# Controlador_PID_digital.net
KiCad netlist of a schematic drawn in EAGLE
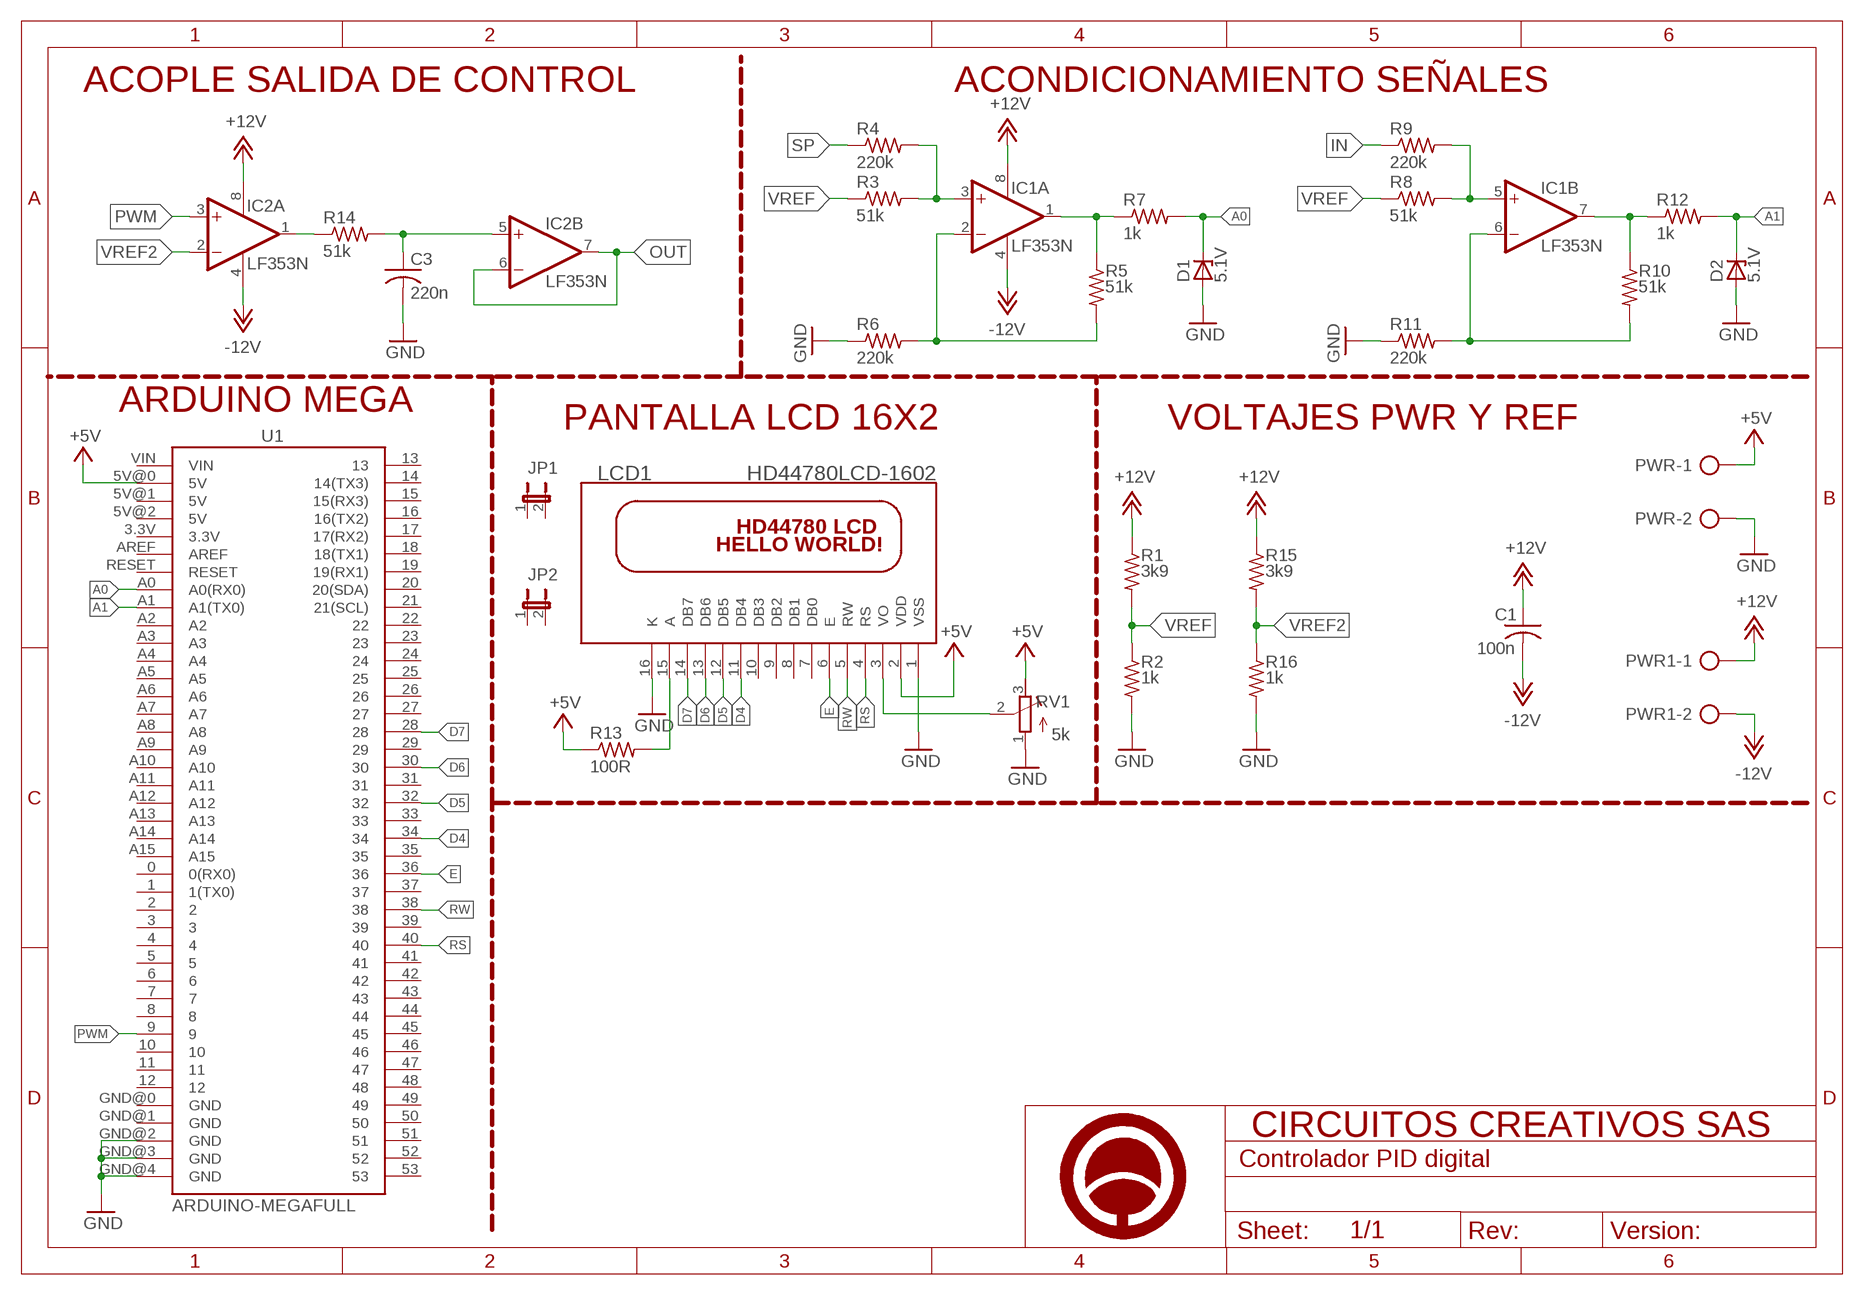
[diagram p0: schematic, sheet 1]

(export (version "E")
  (design (tool "Eeschema 10.0.6"))
  (components
    (comp (ref "C1")
      (value "100n")
      (footprint "eagle-import:C025-025X050")
      (libsource (lib "eagle-import") (part "C-US025-025X050"))
    )
    (comp (ref "C3")
      (value "220n")
      (footprint "eagle-import:C050-030X075")
      (libsource (lib "eagle-import") (part "C-US050-030X075"))
    )
    (comp (ref "D1")
      (value "5.1V")
      (footprint "eagle-import:DO41Z10")
      (libsource (lib "eagle-import") (part "ZENER-DIODEDO41Z10"))
    )
    (comp (ref "D2")
      (value "5.1V")
      (footprint "eagle-import:DO41Z10")
      (libsource (lib "eagle-import") (part "ZENER-DIODEDO41Z10"))
    )
    (comp (ref "IC1")
      (value "LF353N")
      (footprint "eagle-import:DIL08")
      (libsource (lib "eagle-import") (part "LF353N"))
    )
    (comp (ref "IC2")
      (value "LF353N")
      (footprint "eagle-import:DIL08")
      (libsource (lib "eagle-import") (part "LF353N"))
    )
    (comp (ref "JP1")
      (value "JP1E")
      (footprint "eagle-import:JP1")
      (libsource (lib "eagle-import") (part "JP1E"))
    )
    (comp (ref "JP2")
      (value "JP1E")
      (footprint "eagle-import:JP1")
      (libsource (lib "eagle-import") (part "JP1E"))
    )
    (comp (ref "LCD1")
      (value "HD44780LCD-1602")
      (footprint "eagle-import:LCD1602")
      (libsource (lib "eagle-import") (part "HD44780LCD-1602"))
    )
    (comp (ref "PWR")
      (value "AK500/2")
      (footprint "eagle-import:AK500_2")
      (libsource (lib "eagle-import") (part "AK500/2"))
    )
    (comp (ref "PWR1")
      (value "AK500/2")
      (footprint "eagle-import:AK500_2")
      (libsource (lib "eagle-import") (part "AK500/2"))
    )
    (comp (ref "R1")
      (value "3k9")
      (footprint "eagle-import:0204_7")
      (libsource (lib "eagle-import") (part "R-US_0204/7"))
    )
    (comp (ref "R2")
      (value "1k")
      (footprint "eagle-import:0204_7")
      (libsource (lib "eagle-import") (part "R-US_0204/7"))
    )
    (comp (ref "R3")
      (value "51k")
      (footprint "eagle-import:0204_7")
      (libsource (lib "eagle-import") (part "R-US_0204/7"))
    )
    (comp (ref "R4")
      (value "220k")
      (footprint "eagle-import:0204_7")
      (libsource (lib "eagle-import") (part "R-US_0204/7"))
    )
    (comp (ref "R5")
      (value "51k")
      (footprint "eagle-import:0204_7")
      (libsource (lib "eagle-import") (part "R-US_0204/7"))
    )
    (comp (ref "R6")
      (value "220k")
      (footprint "eagle-import:0204_7")
      (libsource (lib "eagle-import") (part "R-US_0204/7"))
    )
    (comp (ref "R7")
      (value "1k")
      (footprint "eagle-import:0204_7")
      (libsource (lib "eagle-import") (part "R-US_0204/7"))
    )
    (comp (ref "R8")
      (value "51k")
      (footprint "eagle-import:0204_7")
      (libsource (lib "eagle-import") (part "R-US_0204/7"))
    )
    (comp (ref "R9")
      (value "220k")
      (footprint "eagle-import:0204_7")
      (libsource (lib "eagle-import") (part "R-US_0204/7"))
    )
    (comp (ref "R10")
      (value "51k")
      (footprint "eagle-import:0204_7")
      (libsource (lib "eagle-import") (part "R-US_0204/7"))
    )
    (comp (ref "R11")
      (value "220k")
      (footprint "eagle-import:0204_7")
      (libsource (lib "eagle-import") (part "R-US_0204/7"))
    )
    (comp (ref "R12")
      (value "1k")
      (footprint "eagle-import:0204_7")
      (libsource (lib "eagle-import") (part "R-US_0204/7"))
    )
    (comp (ref "R13")
      (value "100R")
      (footprint "eagle-import:0204_7")
      (libsource (lib "eagle-import") (part "R-US_0204/7"))
    )
    (comp (ref "R14")
      (value "51k")
      (footprint "eagle-import:0204_7")
      (libsource (lib "eagle-import") (part "R-US_0204/7"))
    )
    (comp (ref "R15")
      (value "3k9")
      (footprint "eagle-import:0204_7")
      (libsource (lib "eagle-import") (part "R-US_0204/7"))
    )
    (comp (ref "R16")
      (value "1k")
      (footprint "eagle-import:0204_7")
      (libsource (lib "eagle-import") (part "R-US_0204/7"))
    )
    (comp (ref "RV1")
      (value "5k")
      (footprint "eagle-import:RTRIM3296W")
      (libsource (lib "eagle-import") (part "R-TRIMM3296W"))
    )
    (comp (ref "U$1")
      (value "A4_HORIZONTAL")
      (footprint "eagle-import:LOGO")
      (libsource (lib "eagle-import") (part "A4_HORIZONTAL"))
    )
    (comp (ref "U1")
      (value "ARDUINO-MEGAFULL")
      (footprint "eagle-import:ARDUINO_MEGA")
      (libsource (lib "eagle-import") (part "ARDUINO-MEGAFULL"))
    )
  )
  (nets
    (net (code "1") (name "+5V") (class "Default")
      (node (ref "LCD1") (pin "2") (pinfunction "VDD_2") (pintype "power_in"))
      (node (ref "PWR") (pin "1") (pinfunction "KL_1") (pintype "passive"))
      (node (ref "R13") (pin "1") (pinfunction "1_1") (pintype "passive"))
      (node (ref "RV1") (pin "3") (pinfunction "E_3") (pintype "passive"))
      (node (ref "U1") (pin "5V@0") (pinfunction "5V_5V@0") (pintype "bidirectional"))
    )
    (net (code "2") (name "+12V") (class "Default")
      (node (ref "C1") (pin "1") (pinfunction "1_1") (pintype "passive"))
      (node (ref "IC1") (pin "8") (pinfunction "V+_8") (pintype "power_in"))
      (node (ref "IC2") (pin "8") (pinfunction "V+_8") (pintype "power_in"))
      (node (ref "PWR1") (pin "1") (pinfunction "KL_1") (pintype "passive"))
      (node (ref "R1") (pin "1") (pinfunction "1_1") (pintype "passive"))
      (node (ref "R15") (pin "1") (pinfunction "1_1") (pintype "passive"))
    )
    (net (code "3") (name "-12V") (class "Default")
      (node (ref "C1") (pin "2") (pinfunction "2_2") (pintype "passive"))
      (node (ref "IC1") (pin "4") (pinfunction "V-_4") (pintype "power_in"))
      (node (ref "IC2") (pin "4") (pinfunction "V-_4") (pintype "power_in"))
      (node (ref "PWR1") (pin "2") (pinfunction "KL_2") (pintype "passive"))
    )
    (net (code "4") (name "A0") (class "Default")
      (node (ref "D1") (pin "C") (pinfunction "C_C") (pintype "passive"))
      (node (ref "R7") (pin "2") (pinfunction "2_2") (pintype "passive"))
      (node (ref "U1") (pin "A0") (pinfunction "A0(RX0)_A0") (pintype "bidirectional"))
    )
    (net (code "5") (name "A1") (class "Default")
      (node (ref "D2") (pin "C") (pinfunction "C_C") (pintype "passive"))
      (node (ref "R12") (pin "2") (pinfunction "2_2") (pintype "passive"))
      (node (ref "U1") (pin "A1") (pinfunction "A1(TX0)_A1") (pintype "bidirectional"))
    )
    (net (code "6") (name "D4") (class "Default")
      (node (ref "LCD1") (pin "11") (pinfunction "DB4_11") (pintype "bidirectional"))
      (node (ref "U1") (pin "34") (pinfunction "34_34") (pintype "bidirectional"))
    )
    (net (code "7") (name "D5") (class "Default")
      (node (ref "LCD1") (pin "12") (pinfunction "DB5_12") (pintype "bidirectional"))
      (node (ref "U1") (pin "32") (pinfunction "32_32") (pintype "bidirectional"))
    )
    (net (code "8") (name "D6") (class "Default")
      (node (ref "LCD1") (pin "13") (pinfunction "DB6_13") (pintype "bidirectional"))
      (node (ref "U1") (pin "30") (pinfunction "30_30") (pintype "bidirectional"))
    )
    (net (code "9") (name "D7") (class "Default")
      (node (ref "LCD1") (pin "14") (pinfunction "DB7_14") (pintype "bidirectional"))
      (node (ref "U1") (pin "28") (pinfunction "28_28") (pintype "bidirectional"))
    )
    (net (code "10") (name "E") (class "Default")
      (node (ref "LCD1") (pin "6") (pinfunction "E_6") (pintype "input"))
      (node (ref "U1") (pin "36") (pinfunction "36_36") (pintype "bidirectional"))
    )
    (net (code "11") (name "GND") (class "Default")
      (node (ref "C3") (pin "2") (pinfunction "2_2") (pintype "passive"))
      (node (ref "D1") (pin "A") (pinfunction "A_A") (pintype "passive"))
      (node (ref "D2") (pin "A") (pinfunction "A_A") (pintype "passive"))
      (node (ref "LCD1") (pin "1") (pinfunction "VSS_1") (pintype "power_in"))
      (node (ref "LCD1") (pin "16") (pinfunction "K_16") (pintype "input"))
      (node (ref "PWR") (pin "2") (pinfunction "KL_2") (pintype "passive"))
      (node (ref "R11") (pin "1") (pinfunction "1_1") (pintype "passive"))
      (node (ref "R16") (pin "2") (pinfunction "2_2") (pintype "passive"))
      (node (ref "R2") (pin "2") (pinfunction "2_2") (pintype "passive"))
      (node (ref "R6") (pin "1") (pinfunction "1_1") (pintype "passive"))
      (node (ref "RV1") (pin "1") (pinfunction "A_1") (pintype "passive"))
      (node (ref "U1") (pin "GND@2") (pinfunction "GND_GND@2") (pintype "bidirectional"))
      (node (ref "U1") (pin "GND@3") (pinfunction "GND_GND@3") (pintype "bidirectional"))
      (node (ref "U1") (pin "GND@4") (pinfunction "GND_GND@4") (pintype "bidirectional"))
    )
    (net (code "12") (name "IN") (class "Default")
      (node (ref "R9") (pin "1") (pinfunction "1_1") (pintype "passive"))
    )
    (net (code "13") (name "Net-(IC1A-+IN)") (class "Default")
      (node (ref "IC1") (pin "3") (pinfunction "+IN_3") (pintype "input"))
      (node (ref "R3") (pin "2") (pinfunction "2_2") (pintype "passive"))
      (node (ref "R4") (pin "2") (pinfunction "2_2") (pintype "passive"))
    )
    (net (code "14") (name "Net-(IC1A--IN)") (class "Default")
      (node (ref "IC1") (pin "2") (pinfunction "-IN_2") (pintype "input"))
      (node (ref "R5") (pin "2") (pinfunction "2_2") (pintype "passive"))
      (node (ref "R6") (pin "2") (pinfunction "2_2") (pintype "passive"))
    )
    (net (code "15") (name "Net-(IC1A-OUT)") (class "Default")
      (node (ref "IC1") (pin "1") (pinfunction "OUT_1") (pintype "output"))
      (node (ref "R5") (pin "1") (pinfunction "1_1") (pintype "passive"))
      (node (ref "R7") (pin "1") (pinfunction "1_1") (pintype "passive"))
    )
    (net (code "16") (name "Net-(IC1B-+IN)") (class "Default")
      (node (ref "IC1") (pin "5") (pinfunction "+IN_5") (pintype "input"))
      (node (ref "R8") (pin "2") (pinfunction "2_2") (pintype "passive"))
      (node (ref "R9") (pin "2") (pinfunction "2_2") (pintype "passive"))
    )
    (net (code "17") (name "Net-(IC1B--IN)") (class "Default")
      (node (ref "IC1") (pin "6") (pinfunction "-IN_6") (pintype "input"))
      (node (ref "R10") (pin "2") (pinfunction "2_2") (pintype "passive"))
      (node (ref "R11") (pin "2") (pinfunction "2_2") (pintype "passive"))
    )
    (net (code "18") (name "Net-(IC1B-OUT)") (class "Default")
      (node (ref "IC1") (pin "7") (pinfunction "OUT_7") (pintype "output"))
      (node (ref "R10") (pin "1") (pinfunction "1_1") (pintype "passive"))
      (node (ref "R12") (pin "1") (pinfunction "1_1") (pintype "passive"))
    )
    (net (code "19") (name "Net-(IC2A-OUT)") (class "Default")
      (node (ref "IC2") (pin "1") (pinfunction "OUT_1") (pintype "output"))
      (node (ref "R14") (pin "1") (pinfunction "1_1") (pintype "passive"))
    )
    (net (code "20") (name "Net-(IC2B-+IN)") (class "Default")
      (node (ref "C3") (pin "1") (pinfunction "1_1") (pintype "passive"))
      (node (ref "IC2") (pin "5") (pinfunction "+IN_5") (pintype "input"))
      (node (ref "R14") (pin "2") (pinfunction "2_2") (pintype "passive"))
    )
    (net (code "21") (name "Net-(LCD1-A)") (class "Default")
      (node (ref "LCD1") (pin "15") (pinfunction "A_15") (pintype "input"))
      (node (ref "R13") (pin "2") (pinfunction "2_2") (pintype "passive"))
    )
    (net (code "22") (name "Net-(LCD1-VO)") (class "Default")
      (node (ref "LCD1") (pin "3") (pinfunction "VO_3") (pintype "input"))
      (node (ref "RV1") (pin "2") (pinfunction "S_2") (pintype "passive"))
    )
    (net (code "23") (name "OUT") (class "Default")
      (node (ref "IC2") (pin "6") (pinfunction "-IN_6") (pintype "input"))
      (node (ref "IC2") (pin "7") (pinfunction "OUT_7") (pintype "output"))
    )
    (net (code "24") (name "PWM") (class "Default")
      (node (ref "IC2") (pin "3") (pinfunction "+IN_3") (pintype "input"))
      (node (ref "U1") (pin "9") (pinfunction "9_9") (pintype "bidirectional"))
    )
    (net (code "25") (name "RS") (class "Default")
      (node (ref "LCD1") (pin "4") (pinfunction "RS_4") (pintype "input"))
      (node (ref "U1") (pin "40") (pinfunction "40_40") (pintype "bidirectional"))
    )
    (net (code "26") (name "RW") (class "Default")
      (node (ref "LCD1") (pin "5") (pinfunction "RW_5") (pintype "input"))
      (node (ref "U1") (pin "38") (pinfunction "38_38") (pintype "bidirectional"))
    )
    (net (code "27") (name "SP") (class "Default")
      (node (ref "R4") (pin "1") (pinfunction "1_1") (pintype "passive"))
    )
    (net (code "28") (name "VREF") (class "Default")
      (node (ref "R1") (pin "2") (pinfunction "2_2") (pintype "passive"))
      (node (ref "R2") (pin "1") (pinfunction "1_1") (pintype "passive"))
      (node (ref "R3") (pin "1") (pinfunction "1_1") (pintype "passive"))
      (node (ref "R8") (pin "1") (pinfunction "1_1") (pintype "passive"))
    )
    (net (code "29") (name "VREF2") (class "Default")
      (node (ref "IC2") (pin "2") (pinfunction "-IN_2") (pintype "input"))
      (node (ref "R15") (pin "2") (pinfunction "2_2") (pintype "passive"))
      (node (ref "R16") (pin "1") (pinfunction "1_1") (pintype "passive"))
    )
    (net (code "30") (name "unconnected-(JP1-Pad1)") (class "Default")
      (node (ref "JP1") (pin "1") (pinfunction "1_1") (pintype "passive"))
    )
    (net (code "31") (name "unconnected-(JP1-Pad2)") (class "Default")
      (node (ref "JP1") (pin "2") (pinfunction "2_2") (pintype "passive"))
    )
    (net (code "32") (name "unconnected-(JP2-Pad1)") (class "Default")
      (node (ref "JP2") (pin "1") (pinfunction "1_1") (pintype "passive"))
    )
    (net (code "33") (name "unconnected-(JP2-Pad2)") (class "Default")
      (node (ref "JP2") (pin "2") (pinfunction "2_2") (pintype "passive"))
    )
    (net (code "34") (name "unconnected-(LCD1-DB0-Pad7)") (class "Default")
      (node (ref "LCD1") (pin "7") (pinfunction "DB0_7") (pintype "bidirectional"))
    )
    (net (code "35") (name "unconnected-(LCD1-DB1-Pad8)") (class "Default")
      (node (ref "LCD1") (pin "8") (pinfunction "DB1_8") (pintype "bidirectional"))
    )
    (net (code "36") (name "unconnected-(LCD1-DB2-Pad9)") (class "Default")
      (node (ref "LCD1") (pin "9") (pinfunction "DB2_9") (pintype "bidirectional"))
    )
    (net (code "37") (name "unconnected-(LCD1-DB3-Pad10)") (class "Default")
      (node (ref "LCD1") (pin "10") (pinfunction "DB3_10") (pintype "bidirectional"))
    )
    (net (code "38") (name "unconnected-(U1-0(RX0)-Pad0)") (class "Default")
      (node (ref "U1") (pin "0") (pinfunction "0(RX0)_0") (pintype "bidirectional"))
    )
    (net (code "39") (name "unconnected-(U1-1(TX0)-Pad1)") (class "Default")
      (node (ref "U1") (pin "1") (pinfunction "1(TX0)_1") (pintype "bidirectional"))
    )
    (net (code "40") (name "unconnected-(U1-5V-Pad5V@1)") (class "Default")
      (node (ref "U1") (pin "5V@1") (pinfunction "5V_5V@1") (pintype "bidirectional"))
    )
    (net (code "41") (name "unconnected-(U1-5V-Pad5V@2)") (class "Default")
      (node (ref "U1") (pin "5V@2") (pinfunction "5V_5V@2") (pintype "bidirectional"))
    )
    (net (code "42") (name "unconnected-(U1-14(TX3)-Pad14)") (class "Default")
      (node (ref "U1") (pin "14") (pinfunction "14(TX3)_14") (pintype "bidirectional"))
    )
    (net (code "43") (name "unconnected-(U1-15(RX3)-Pad15)") (class "Default")
      (node (ref "U1") (pin "15") (pinfunction "15(RX3)_15") (pintype "bidirectional"))
    )
    (net (code "44") (name "unconnected-(U1-16(TX2)-Pad16)") (class "Default")
      (node (ref "U1") (pin "16") (pinfunction "16(TX2)_16") (pintype "bidirectional"))
    )
    (net (code "45") (name "unconnected-(U1-17(RX2)-Pad17)") (class "Default")
      (node (ref "U1") (pin "17") (pinfunction "17(RX2)_17") (pintype "bidirectional"))
    )
    (net (code "46") (name "unconnected-(U1-18(TX1)-Pad18)") (class "Default")
      (node (ref "U1") (pin "18") (pinfunction "18(TX1)_18") (pintype "bidirectional"))
    )
    (net (code "47") (name "unconnected-(U1-19(RX1)-Pad19)") (class "Default")
      (node (ref "U1") (pin "19") (pinfunction "19(RX1)_19") (pintype "bidirectional"))
    )
    (net (code "48") (name "unconnected-(U1-20(SDA)-Pad20)") (class "Default")
      (node (ref "U1") (pin "20") (pinfunction "20(SDA)_20") (pintype "bidirectional"))
    )
    (net (code "49") (name "unconnected-(U1-21(SCL)-Pad21)") (class "Default")
      (node (ref "U1") (pin "21") (pinfunction "21(SCL)_21") (pintype "bidirectional"))
    )
    (net (code "50") (name "unconnected-(U1-GND-PadGND@0)") (class "Default")
      (node (ref "U1") (pin "GND@0") (pinfunction "GND_GND@0") (pintype "bidirectional"))
    )
    (net (code "51") (name "unconnected-(U1-GND-PadGND@1)") (class "Default")
      (node (ref "U1") (pin "GND@1") (pinfunction "GND_GND@1") (pintype "bidirectional"))
    )
    (net (code "52") (name "unconnected-(U1-Pad2)") (class "Default")
      (node (ref "U1") (pin "2") (pinfunction "2_2") (pintype "bidirectional"))
    )
    (net (code "53") (name "unconnected-(U1-Pad3)") (class "Default")
      (node (ref "U1") (pin "3") (pinfunction "3_3") (pintype "bidirectional"))
    )
    (net (code "54") (name "unconnected-(U1-Pad3.3V)") (class "Default")
      (node (ref "U1") (pin "3.3V") (pinfunction "3.3V_3.3V") (pintype "bidirectional"))
    )
    (net (code "55") (name "unconnected-(U1-Pad4)") (class "Default")
      (node (ref "U1") (pin "4") (pinfunction "4_4") (pintype "bidirectional"))
    )
    (net (code "56") (name "unconnected-(U1-Pad5)") (class "Default")
      (node (ref "U1") (pin "5") (pinfunction "5_5") (pintype "bidirectional"))
    )
    (net (code "57") (name "unconnected-(U1-Pad6)") (class "Default")
      (node (ref "U1") (pin "6") (pinfunction "6_6") (pintype "bidirectional"))
    )
    (net (code "58") (name "unconnected-(U1-Pad7)") (class "Default")
      (node (ref "U1") (pin "7") (pinfunction "7_7") (pintype "bidirectional"))
    )
    (net (code "59") (name "unconnected-(U1-Pad8)") (class "Default")
      (node (ref "U1") (pin "8") (pinfunction "8_8") (pintype "bidirectional"))
    )
    (net (code "60") (name "unconnected-(U1-Pad10)") (class "Default")
      (node (ref "U1") (pin "10") (pinfunction "10_10") (pintype "bidirectional"))
    )
    (net (code "61") (name "unconnected-(U1-Pad11)") (class "Default")
      (node (ref "U1") (pin "11") (pinfunction "11_11") (pintype "bidirectional"))
    )
    (net (code "62") (name "unconnected-(U1-Pad12)") (class "Default")
      (node (ref "U1") (pin "12") (pinfunction "12_12") (pintype "bidirectional"))
    )
    (net (code "63") (name "unconnected-(U1-Pad13)") (class "Default")
      (node (ref "U1") (pin "13") (pinfunction "13_13") (pintype "bidirectional"))
    )
    (net (code "64") (name "unconnected-(U1-Pad22)") (class "Default")
      (node (ref "U1") (pin "22") (pinfunction "22_22") (pintype "bidirectional"))
    )
    (net (code "65") (name "unconnected-(U1-Pad23)") (class "Default")
      (node (ref "U1") (pin "23") (pinfunction "23_23") (pintype "bidirectional"))
    )
    (net (code "66") (name "unconnected-(U1-Pad24)") (class "Default")
      (node (ref "U1") (pin "24") (pinfunction "24_24") (pintype "bidirectional"))
    )
    (net (code "67") (name "unconnected-(U1-Pad25)") (class "Default")
      (node (ref "U1") (pin "25") (pinfunction "25_25") (pintype "bidirectional"))
    )
    (net (code "68") (name "unconnected-(U1-Pad26)") (class "Default")
      (node (ref "U1") (pin "26") (pinfunction "26_26") (pintype "bidirectional"))
    )
    (net (code "69") (name "unconnected-(U1-Pad27)") (class "Default")
      (node (ref "U1") (pin "27") (pinfunction "27_27") (pintype "bidirectional"))
    )
    (net (code "70") (name "unconnected-(U1-Pad29)") (class "Default")
      (node (ref "U1") (pin "29") (pinfunction "29_29") (pintype "bidirectional"))
    )
    (net (code "71") (name "unconnected-(U1-Pad31)") (class "Default")
      (node (ref "U1") (pin "31") (pinfunction "31_31") (pintype "bidirectional"))
    )
    (net (code "72") (name "unconnected-(U1-Pad33)") (class "Default")
      (node (ref "U1") (pin "33") (pinfunction "33_33") (pintype "bidirectional"))
    )
    (net (code "73") (name "unconnected-(U1-Pad35)") (class "Default")
      (node (ref "U1") (pin "35") (pinfunction "35_35") (pintype "bidirectional"))
    )
    (net (code "74") (name "unconnected-(U1-Pad37)") (class "Default")
      (node (ref "U1") (pin "37") (pinfunction "37_37") (pintype "bidirectional"))
    )
    (net (code "75") (name "unconnected-(U1-Pad39)") (class "Default")
      (node (ref "U1") (pin "39") (pinfunction "39_39") (pintype "bidirectional"))
    )
    (net (code "76") (name "unconnected-(U1-Pad41)") (class "Default")
      (node (ref "U1") (pin "41") (pinfunction "41_41") (pintype "bidirectional"))
    )
    (net (code "77") (name "unconnected-(U1-Pad42)") (class "Default")
      (node (ref "U1") (pin "42") (pinfunction "42_42") (pintype "bidirectional"))
    )
    (net (code "78") (name "unconnected-(U1-Pad43)") (class "Default")
      (node (ref "U1") (pin "43") (pinfunction "43_43") (pintype "bidirectional"))
    )
    (net (code "79") (name "unconnected-(U1-Pad44)") (class "Default")
      (node (ref "U1") (pin "44") (pinfunction "44_44") (pintype "bidirectional"))
    )
    (net (code "80") (name "unconnected-(U1-Pad45)") (class "Default")
      (node (ref "U1") (pin "45") (pinfunction "45_45") (pintype "bidirectional"))
    )
    (net (code "81") (name "unconnected-(U1-Pad46)") (class "Default")
      (node (ref "U1") (pin "46") (pinfunction "46_46") (pintype "bidirectional"))
    )
    (net (code "82") (name "unconnected-(U1-Pad47)") (class "Default")
      (node (ref "U1") (pin "47") (pinfunction "47_47") (pintype "bidirectional"))
    )
    (net (code "83") (name "unconnected-(U1-Pad48)") (class "Default")
      (node (ref "U1") (pin "48") (pinfunction "48_48") (pintype "bidirectional"))
    )
    (net (code "84") (name "unconnected-(U1-Pad49)") (class "Default")
      (node (ref "U1") (pin "49") (pinfunction "49_49") (pintype "bidirectional"))
    )
    (net (code "85") (name "unconnected-(U1-Pad50)") (class "Default")
      (node (ref "U1") (pin "50") (pinfunction "50_50") (pintype "bidirectional"))
    )
    (net (code "86") (name "unconnected-(U1-Pad51)") (class "Default")
      (node (ref "U1") (pin "51") (pinfunction "51_51") (pintype "bidirectional"))
    )
    (net (code "87") (name "unconnected-(U1-Pad52)") (class "Default")
      (node (ref "U1") (pin "52") (pinfunction "52_52") (pintype "bidirectional"))
    )
    (net (code "88") (name "unconnected-(U1-Pad53)") (class "Default")
      (node (ref "U1") (pin "53") (pinfunction "53_53") (pintype "bidirectional"))
    )
    (net (code "89") (name "unconnected-(U1-PadA2)") (class "Default")
      (node (ref "U1") (pin "A2") (pinfunction "A2_A2") (pintype "bidirectional"))
    )
    (net (code "90") (name "unconnected-(U1-PadA3)") (class "Default")
      (node (ref "U1") (pin "A3") (pinfunction "A3_A3") (pintype "bidirectional"))
    )
    (net (code "91") (name "unconnected-(U1-PadA4)") (class "Default")
      (node (ref "U1") (pin "A4") (pinfunction "A4_A4") (pintype "bidirectional"))
    )
    (net (code "92") (name "unconnected-(U1-PadA5)") (class "Default")
      (node (ref "U1") (pin "A5") (pinfunction "A5_A5") (pintype "bidirectional"))
    )
    (net (code "93") (name "unconnected-(U1-PadA6)") (class "Default")
      (node (ref "U1") (pin "A6") (pinfunction "A6_A6") (pintype "bidirectional"))
    )
    (net (code "94") (name "unconnected-(U1-PadA7)") (class "Default")
      (node (ref "U1") (pin "A7") (pinfunction "A7_A7") (pintype "bidirectional"))
    )
    (net (code "95") (name "unconnected-(U1-PadA8)") (class "Default")
      (node (ref "U1") (pin "A8") (pinfunction "A8_A8") (pintype "bidirectional"))
    )
    (net (code "96") (name "unconnected-(U1-PadA9)") (class "Default")
      (node (ref "U1") (pin "A9") (pinfunction "A9_A9") (pintype "bidirectional"))
    )
    (net (code "97") (name "unconnected-(U1-PadA10)") (class "Default")
      (node (ref "U1") (pin "A10") (pinfunction "A10_A10") (pintype "bidirectional"))
    )
    (net (code "98") (name "unconnected-(U1-PadA11)") (class "Default")
      (node (ref "U1") (pin "A11") (pinfunction "A11_A11") (pintype "bidirectional"))
    )
    (net (code "99") (name "unconnected-(U1-PadA12)") (class "Default")
      (node (ref "U1") (pin "A12") (pinfunction "A12_A12") (pintype "bidirectional"))
    )
    (net (code "100") (name "unconnected-(U1-PadA13)") (class "Default")
      (node (ref "U1") (pin "A13") (pinfunction "A13_A13") (pintype "bidirectional"))
    )
    (net (code "101") (name "unconnected-(U1-PadA14)") (class "Default")
      (node (ref "U1") (pin "A14") (pinfunction "A14_A14") (pintype "bidirectional"))
    )
    (net (code "102") (name "unconnected-(U1-PadA15)") (class "Default")
      (node (ref "U1") (pin "A15") (pinfunction "A15_A15") (pintype "bidirectional"))
    )
    (net (code "103") (name "unconnected-(U1-PadAREF)") (class "Default")
      (node (ref "U1") (pin "AREF") (pinfunction "AREF_AREF") (pintype "bidirectional"))
    )
    (net (code "104") (name "unconnected-(U1-PadRESET)") (class "Default")
      (node (ref "U1") (pin "RESET") (pinfunction "RESET_RESET") (pintype "bidirectional"))
    )
    (net (code "105") (name "unconnected-(U1-PadVIN)") (class "Default")
      (node (ref "U1") (pin "VIN") (pinfunction "VIN_VIN") (pintype "bidirectional"))
    )
  )
)
